# EEPROM_and_Temperature_Sensor.net
KiCad netlist of a schematic drawn in Altium Designer
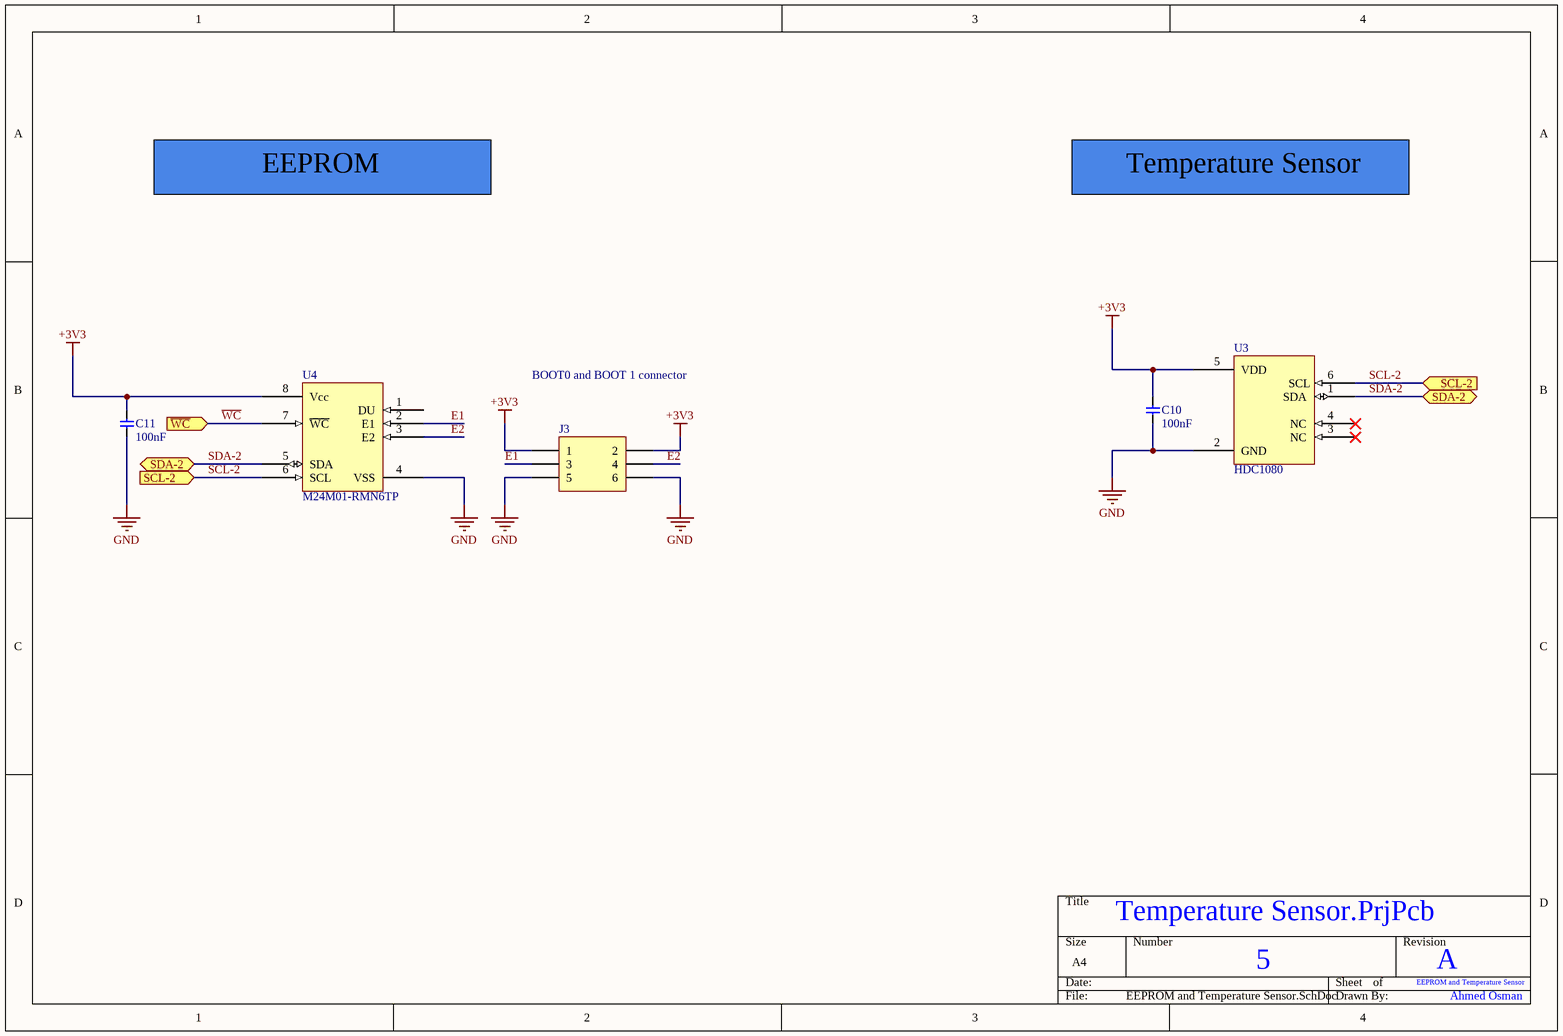
[diagram p0: EEPROM and Temperature Sensor.SchDoc]

(export (version "E")
  (design (tool "Eeschema 10.0.6"))
  (components
    (comp (ref "C10")
      (value "100nF")
      (footprint "CAP 0603")
      (description "0.1 µF ±10% 50V Ceramic Capacitor X7R 0603 (1608 Metric)")
      (fields (field (name "TOLERANCE") "10%") (field (name "VOLTAGE") "50V"))
      (libsource (lib "Temperature project symbols") (part "CAP  0603 100nF 10% 50 V"))
    )
    (comp (ref "C11")
      (value "100nF")
      (footprint "CAP 0603")
      (description "0.1 µF ±10% 50V Ceramic Capacitor X7R 0603 (1608 Metric)")
      (fields (field (name "TOLERANCE") "10%") (field (name "VOLTAGE") "50V"))
      (libsource (lib "Temperature project symbols") (part "CAP  0603 100nF 10% 50 V"))
    )
    (comp (ref "J3")
      (value "BOOT0 and BOOT 1 connector")
      (footprint "2X3 Female Pin Header Connector")
      (libsource (lib "Temperature project symbols") (part "BOOT0 and BOOT 1 connector"))
    )
    (comp (ref "U3")
      (value "HDC1080")
      (footprint "PWSON(6-pin) DMB")
      (description "Humidity, Temperature 0 ~ 100% RH I2C ±2% RH 15 s Surface Mount")
      (libsource (lib "Temperature project symbols") (part "HDC1080"))
    )
    (comp (ref "U4")
      (value "M24M01-RMN6TP")
      (footprint "SO8N")
      (description "EEPROM Memory IC 1Mbit I2C 1 MHz 500 ns 8-SOIC")
      (libsource (lib "Temperature project symbols") (part "M24M01-RMN6TP"))
    )
  )
  (nets
    (net (code "1") (name "+3V3") (class "Default")
      (node (ref "C10") (pin "2") (pintype "passive"))
      (node (ref "C11") (pin "1") (pintype "passive"))
      (node (ref "J3") (pin "1") (pinfunction "1_1") (pintype "passive"))
      (node (ref "J3") (pin "2") (pinfunction "2_2") (pintype "passive"))
      (node (ref "U3") (pin "5") (pinfunction "VDD_5") (pintype "power_in"))
      (node (ref "U4") (pin "8") (pinfunction "Vcc_8") (pintype "power_in"))
    )
    (net (code "2") (name "/E1") (class "Default")
      (node (ref "J3") (pin "3") (pinfunction "3_3") (pintype "passive"))
      (node (ref "U4") (pin "2") (pinfunction "E1_2") (pintype "input"))
    )
    (net (code "3") (name "/E2") (class "Default")
      (node (ref "J3") (pin "4") (pinfunction "4_4") (pintype "passive"))
      (node (ref "U4") (pin "3") (pinfunction "E2_3") (pintype "input"))
    )
    (net (code "4") (name "/SCL-2") (class "Default")
      (node (ref "U3") (pin "6") (pinfunction "SCL_6") (pintype "input"))
      (node (ref "U4") (pin "6") (pinfunction "SCL_6") (pintype "input"))
    )
    (net (code "5") (name "/SDA-2") (class "Default")
      (node (ref "U3") (pin "1") (pinfunction "SDA_1") (pintype "bidirectional"))
      (node (ref "U4") (pin "5") (pinfunction "SDA_5") (pintype "bidirectional"))
    )
    (net (code "6") (name "/~{WC}") (class "Default")
      (node (ref "U4") (pin "7") (pinfunction "~{WC}_7") (pintype "input"))
    )
    (net (code "7") (name "GND") (class "Default")
      (node (ref "C10") (pin "1") (pintype "passive"))
      (node (ref "C11") (pin "2") (pintype "passive"))
      (node (ref "J3") (pin "5") (pinfunction "5_5") (pintype "passive"))
      (node (ref "J3") (pin "6") (pinfunction "6_6") (pintype "passive"))
      (node (ref "U3") (pin "2") (pinfunction "GND_2") (pintype "power_in"))
      (node (ref "U4") (pin "4") (pinfunction "VSS_4") (pintype "power_in"))
    )
    (net (code "8") (name "unconnected-(U3-NC-Pad3)") (class "Default")
      (node (ref "U3") (pin "3") (pinfunction "NC_3") (pintype "input+no_connect"))
    )
    (net (code "9") (name "unconnected-(U3-NC-Pad4)") (class "Default")
      (node (ref "U3") (pin "4") (pinfunction "NC_4") (pintype "input+no_connect"))
    )
    (net (code "10") (name "unconnected-(U4-DU-Pad1)") (class "Default")
      (node (ref "U4") (pin "1") (pinfunction "DU_1") (pintype "input"))
    )
  )
)
